# OUTPUT.net
KiCad netlist of a schematic drawn in Altium Designer
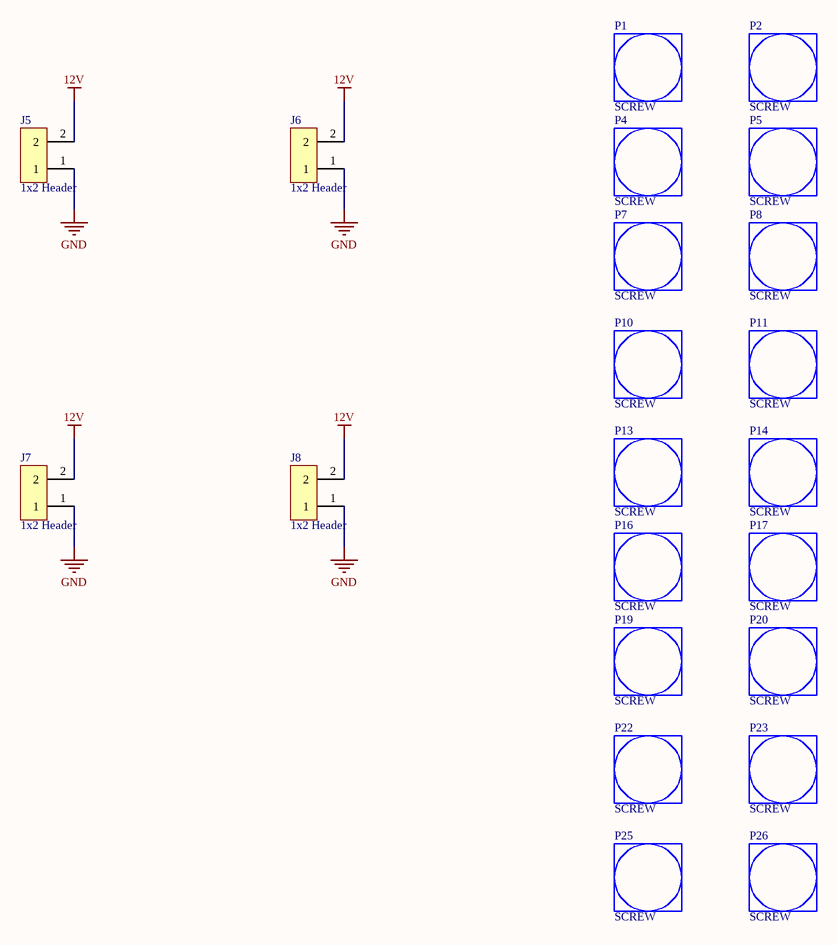
[diagram p0: OUTPUT.SchDoc]

(export (version "E")
  (design (tool "Eeschema 10.0.6"))
  (components
    (comp (ref "J5")
      (value "1x2 Header")
      (footprint "HDR1*2")
      (description "Headers & Wire Housings 2 PIN F/LK HEADER")
      (fields (field (name "MANUFACTURER") "Molex") (field (name "MANUFACTURER PART NUMBER") "22-29-2021"))
      (libsource (lib "Miner_8TH") (part "HDR1*2"))
    )
    (comp (ref "J6")
      (value "1x2 Header")
      (footprint "HDR1*2")
      (description "Headers & Wire Housings 2 PIN F/LK HEADER")
      (fields (field (name "MANUFACTURER") "Molex") (field (name "MANUFACTURER PART NUMBER") "22-29-2021"))
      (libsource (lib "Miner_8TH") (part "HDR1*2"))
    )
    (comp (ref "J7")
      (value "1x2 Header")
      (footprint "HDR1*2")
      (description "Headers & Wire Housings 2 PIN F/LK HEADER")
      (fields (field (name "MANUFACTURER") "Molex") (field (name "MANUFACTURER PART NUMBER") "22-29-2021"))
      (libsource (lib "Miner_8TH") (part "HDR1*2"))
    )
    (comp (ref "J8")
      (value "1x2 Header")
      (footprint "HDR1*2")
      (description "Headers & Wire Housings 2 PIN F/LK HEADER")
      (fields (field (name "MANUFACTURER") "Molex") (field (name "MANUFACTURER PART NUMBER") "22-29-2021"))
      (libsource (lib "Miner_8TH") (part "HDR1*2"))
    )
    (comp (ref "P1") (value "SCREW") (footprint "PICH") (libsource (lib "Miner_8TH") (part "PICH")))
    (comp (ref "P2") (value "SCREW") (footprint "PICH") (libsource (lib "Miner_8TH") (part "PICH")))
    (comp (ref "P4") (value "SCREW") (footprint "PICH") (libsource (lib "Miner_8TH") (part "PICH")))
    (comp (ref "P5") (value "SCREW") (footprint "PICH") (libsource (lib "Miner_8TH") (part "PICH")))
    (comp (ref "P7") (value "SCREW") (footprint "PICH") (libsource (lib "Miner_8TH") (part "PICH")))
    (comp (ref "P8") (value "SCREW") (footprint "PICH") (libsource (lib "Miner_8TH") (part "PICH")))
    (comp (ref "P10") (value "SCREW") (footprint "PICH") (libsource (lib "Miner_8TH") (part "PICH")))
    (comp (ref "P11") (value "SCREW") (footprint "PICH") (libsource (lib "Miner_8TH") (part "PICH")))
    (comp (ref "P13") (value "SCREW") (footprint "PICH") (libsource (lib "Miner_8TH") (part "PICH")))
    (comp (ref "P14") (value "SCREW") (footprint "PICH") (libsource (lib "Miner_8TH") (part "PICH")))
    (comp (ref "P16") (value "SCREW") (footprint "PICH") (libsource (lib "Miner_8TH") (part "PICH")))
    (comp (ref "P17") (value "SCREW") (footprint "PICH") (libsource (lib "Miner_8TH") (part "PICH")))
    (comp (ref "P19") (value "SCREW") (footprint "PICH") (libsource (lib "Miner_8TH") (part "PICH")))
    (comp (ref "P20") (value "SCREW") (footprint "PICH") (libsource (lib "Miner_8TH") (part "PICH")))
    (comp (ref "P22") (value "SCREW") (footprint "PICH") (libsource (lib "Miner_8TH") (part "PICH")))
    (comp (ref "P23") (value "SCREW") (footprint "PICH") (libsource (lib "Miner_8TH") (part "PICH")))
    (comp (ref "P25") (value "SCREW") (footprint "PICH") (libsource (lib "Miner_8TH") (part "PICH")))
    (comp (ref "P26") (value "SCREW") (footprint "PICH") (libsource (lib "Miner_8TH") (part "PICH")))
  )
  (nets
    (net (code "1") (name "12V") (class "Default")
      (node (ref "J5") (pin "2") (pinfunction "2_2") (pintype "passive"))
      (node (ref "J6") (pin "2") (pinfunction "2_2") (pintype "passive"))
      (node (ref "J7") (pin "2") (pinfunction "2_2") (pintype "passive"))
      (node (ref "J8") (pin "2") (pinfunction "2_2") (pintype "passive"))
    )
    (net (code "2") (name "GND") (class "Default")
      (node (ref "J5") (pin "1") (pinfunction "1_1") (pintype "passive"))
      (node (ref "J6") (pin "1") (pinfunction "1_1") (pintype "passive"))
      (node (ref "J7") (pin "1") (pinfunction "1_1") (pintype "passive"))
      (node (ref "J8") (pin "1") (pinfunction "1_1") (pintype "passive"))
    )
  )
)
